# B-CAN_Board.net
KiCad netlist of a schematic drawn in EAGLE
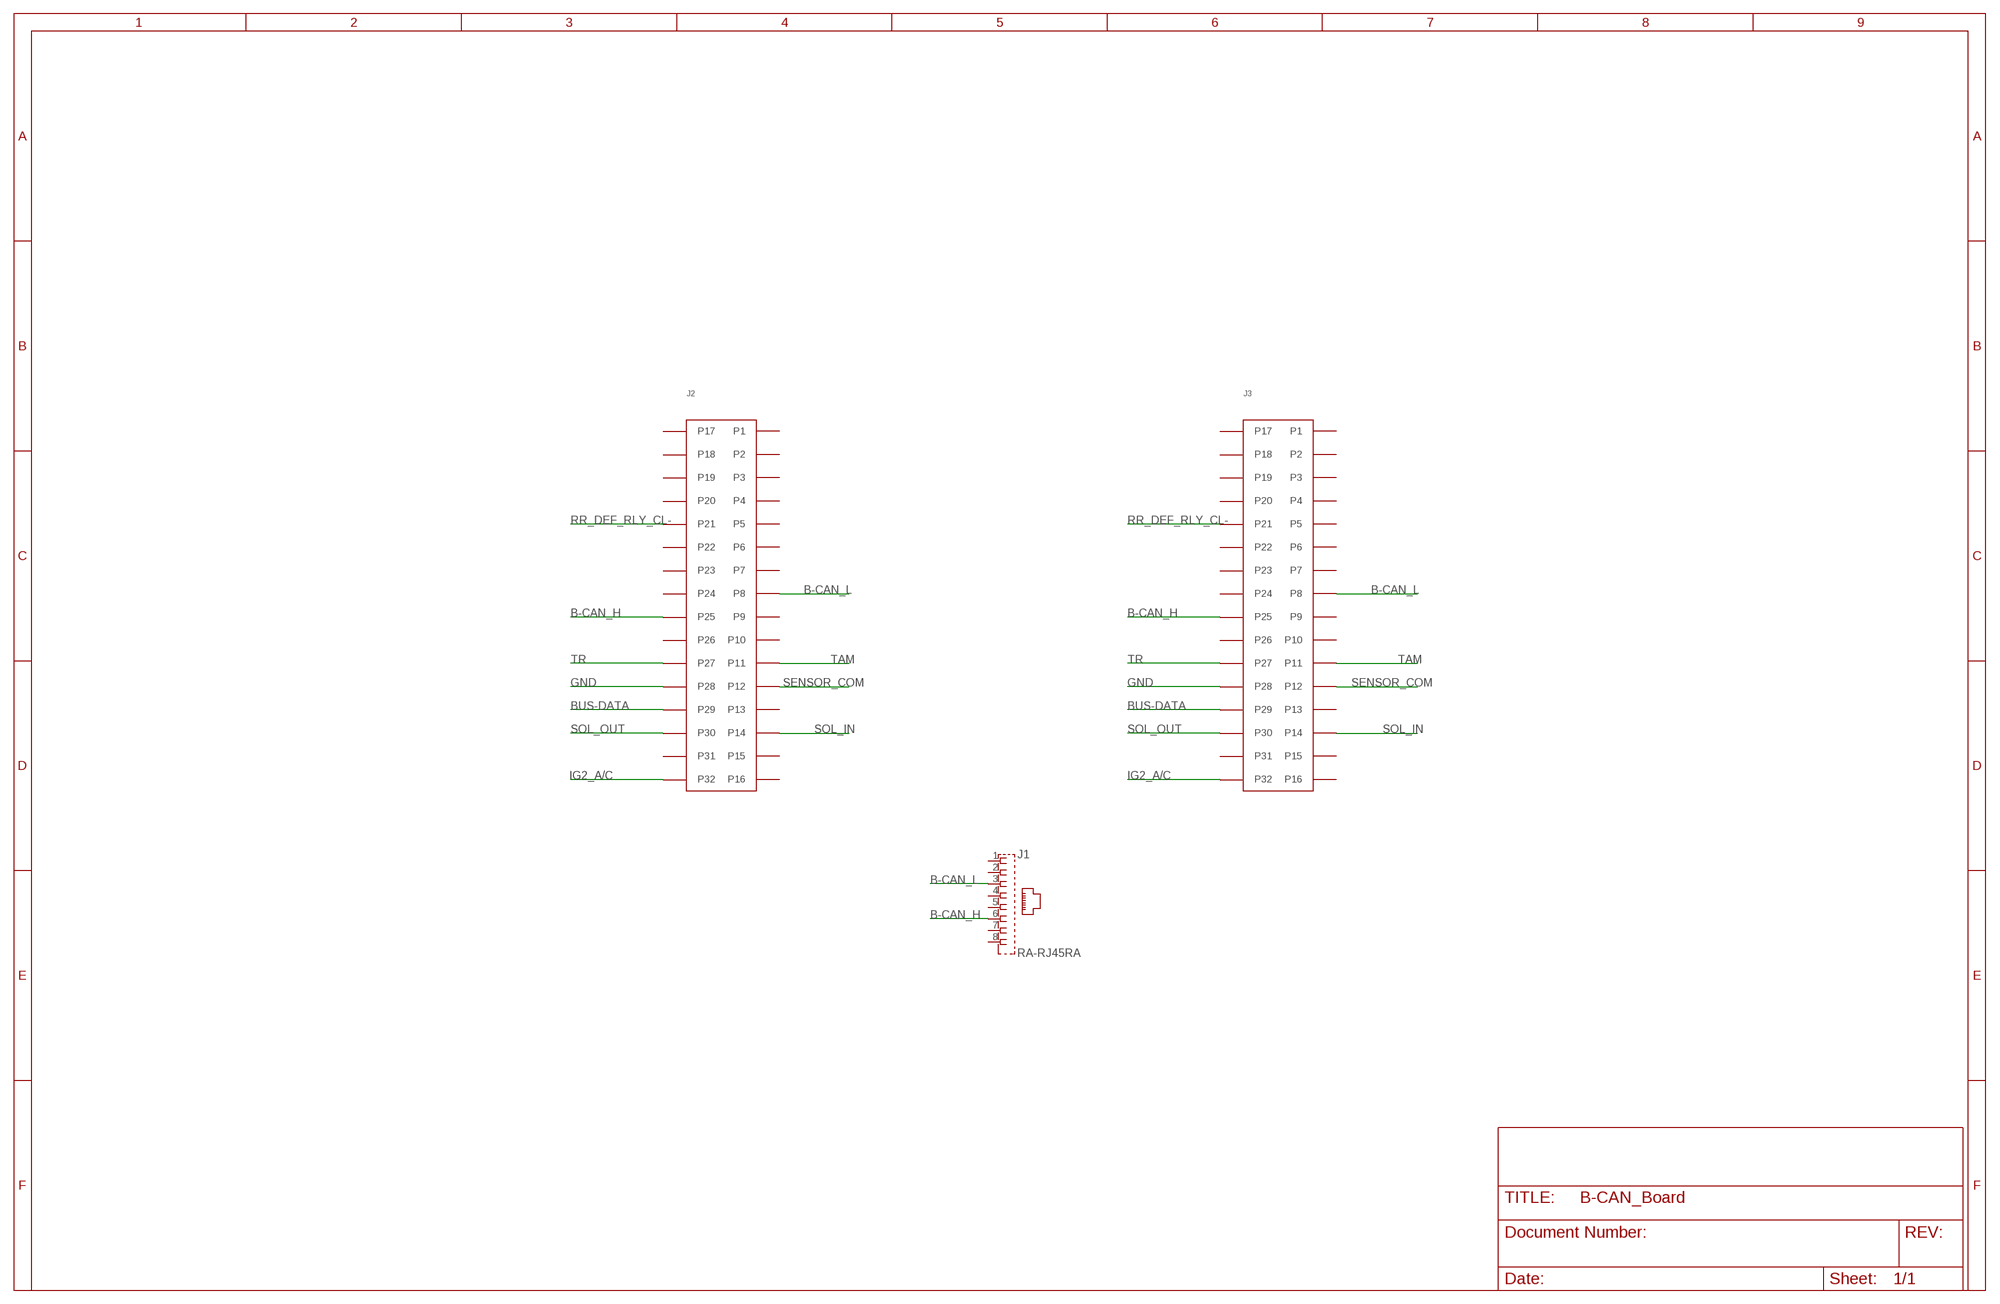
[diagram p0: schematic, sheet 1]

(export (version "E")
  (design (tool "Eeschema 10.0.6"))
  (components
    (comp (ref "J1")
      (value "RA-RJ45RA")
      (footprint "eagle-import:RA-RJ45")
      (libsource (lib "eagle-import") (part "RA-RJ45RA"))
    )
    (comp (ref "J2")
      (value "MX34032UF2")
      (footprint "eagle-import:MX34032UF2")
      (libsource (lib "eagle-import") (part "MX34032UF2"))
    )
    (comp (ref "J3")
      (value "MX34032UF2")
      (footprint "eagle-import:MX34032UF2")
      (libsource (lib "eagle-import") (part "MX34032UF2"))
    )
  )
  (nets
    (net (code "1") (name "/B-CAN_H") (class "Default")
      (node (ref "J1") (pin "6") (pinfunction "6_6") (pintype "passive"))
      (node (ref "J2") (pin "P25") (pinfunction "P25_P25") (pintype "bidirectional"))
      (node (ref "J3") (pin "P25") (pinfunction "P25_P25") (pintype "bidirectional"))
    )
    (net (code "2") (name "/B-CAN_L") (class "Default")
      (node (ref "J1") (pin "3") (pinfunction "3_3") (pintype "passive"))
      (node (ref "J2") (pin "P8") (pinfunction "P8_P8") (pintype "bidirectional"))
      (node (ref "J3") (pin "P8") (pinfunction "P8_P8") (pintype "bidirectional"))
    )
    (net (code "3") (name "/BUS-DATA") (class "Default")
      (node (ref "J2") (pin "P29") (pinfunction "P29_P29") (pintype "bidirectional"))
      (node (ref "J3") (pin "P29") (pinfunction "P29_P29") (pintype "bidirectional"))
    )
    (net (code "4") (name "/GND") (class "Default")
      (node (ref "J2") (pin "P28") (pinfunction "P28_P28") (pintype "bidirectional"))
      (node (ref "J3") (pin "P28") (pinfunction "P28_P28") (pintype "bidirectional"))
    )
    (net (code "5") (name "/IG2_A{slash}C") (class "Default")
      (node (ref "J2") (pin "P32") (pinfunction "P32_P32") (pintype "bidirectional"))
      (node (ref "J3") (pin "P32") (pinfunction "P32_P32") (pintype "bidirectional"))
    )
    (net (code "6") (name "/RR_DEF_RLY_CL-") (class "Default")
      (node (ref "J2") (pin "P21") (pinfunction "P21_P21") (pintype "bidirectional"))
      (node (ref "J3") (pin "P21") (pinfunction "P21_P21") (pintype "bidirectional"))
    )
    (net (code "7") (name "/SENSOR_COM") (class "Default")
      (node (ref "J2") (pin "P12") (pinfunction "P12_P12") (pintype "bidirectional"))
      (node (ref "J3") (pin "P12") (pinfunction "P12_P12") (pintype "bidirectional"))
    )
    (net (code "8") (name "/SOL_IN") (class "Default")
      (node (ref "J2") (pin "P14") (pinfunction "P14_P14") (pintype "bidirectional"))
      (node (ref "J3") (pin "P14") (pinfunction "P14_P14") (pintype "bidirectional"))
    )
    (net (code "9") (name "/SOL_OUT") (class "Default")
      (node (ref "J2") (pin "P30") (pinfunction "P30_P30") (pintype "bidirectional"))
      (node (ref "J3") (pin "P30") (pinfunction "P30_P30") (pintype "bidirectional"))
    )
    (net (code "10") (name "/TAM") (class "Default")
      (node (ref "J2") (pin "P11") (pinfunction "P11_P11") (pintype "bidirectional"))
      (node (ref "J3") (pin "P11") (pinfunction "P11_P11") (pintype "bidirectional"))
    )
    (net (code "11") (name "/TR") (class "Default")
      (node (ref "J2") (pin "P27") (pinfunction "P27_P27") (pintype "bidirectional"))
      (node (ref "J3") (pin "P27") (pinfunction "P27_P27") (pintype "bidirectional"))
    )
    (net (code "12") (name "unconnected-(J1-Pad1)") (class "Default")
      (node (ref "J1") (pin "1") (pinfunction "1_1") (pintype "passive"))
    )
    (net (code "13") (name "unconnected-(J1-Pad2)") (class "Default")
      (node (ref "J1") (pin "2") (pinfunction "2_2") (pintype "passive"))
    )
    (net (code "14") (name "unconnected-(J1-Pad4)") (class "Default")
      (node (ref "J1") (pin "4") (pinfunction "4_4") (pintype "passive"))
    )
    (net (code "15") (name "unconnected-(J1-Pad5)") (class "Default")
      (node (ref "J1") (pin "5") (pinfunction "5_5") (pintype "passive"))
    )
    (net (code "16") (name "unconnected-(J1-Pad7)") (class "Default")
      (node (ref "J1") (pin "7") (pinfunction "7_7") (pintype "passive"))
    )
    (net (code "17") (name "unconnected-(J1-Pad8)") (class "Default")
      (node (ref "J1") (pin "8") (pinfunction "8_8") (pintype "passive"))
    )
    (net (code "18") (name "unconnected-(J2-PadP1)") (class "Default")
      (node (ref "J2") (pin "P1") (pinfunction "P1_P1") (pintype "bidirectional"))
    )
    (net (code "19") (name "unconnected-(J2-PadP2)") (class "Default")
      (node (ref "J2") (pin "P2") (pinfunction "P2_P2") (pintype "bidirectional"))
    )
    (net (code "20") (name "unconnected-(J2-PadP3)") (class "Default")
      (node (ref "J2") (pin "P3") (pinfunction "P3_P3") (pintype "bidirectional"))
    )
    (net (code "21") (name "unconnected-(J2-PadP4)") (class "Default")
      (node (ref "J2") (pin "P4") (pinfunction "P4_P4") (pintype "bidirectional"))
    )
    (net (code "22") (name "unconnected-(J2-PadP5)") (class "Default")
      (node (ref "J2") (pin "P5") (pinfunction "P5_P5") (pintype "bidirectional"))
    )
    (net (code "23") (name "unconnected-(J2-PadP6)") (class "Default")
      (node (ref "J2") (pin "P6") (pinfunction "P6_P6") (pintype "bidirectional"))
    )
    (net (code "24") (name "unconnected-(J2-PadP7)") (class "Default")
      (node (ref "J2") (pin "P7") (pinfunction "P7_P7") (pintype "bidirectional"))
    )
    (net (code "25") (name "unconnected-(J2-PadP9)") (class "Default")
      (node (ref "J2") (pin "P9") (pinfunction "P9_P9") (pintype "bidirectional"))
    )
    (net (code "26") (name "unconnected-(J2-PadP10)") (class "Default")
      (node (ref "J2") (pin "P10") (pinfunction "P10_P10") (pintype "bidirectional"))
    )
    (net (code "27") (name "unconnected-(J2-PadP13)") (class "Default")
      (node (ref "J2") (pin "P13") (pinfunction "P13_P13") (pintype "bidirectional"))
    )
    (net (code "28") (name "unconnected-(J2-PadP15)") (class "Default")
      (node (ref "J2") (pin "P15") (pinfunction "P15_P15") (pintype "bidirectional"))
    )
    (net (code "29") (name "unconnected-(J2-PadP16)") (class "Default")
      (node (ref "J2") (pin "P16") (pinfunction "P16_P16") (pintype "bidirectional"))
    )
    (net (code "30") (name "unconnected-(J2-PadP17)") (class "Default")
      (node (ref "J2") (pin "P17") (pinfunction "P17_P17") (pintype "bidirectional"))
    )
    (net (code "31") (name "unconnected-(J2-PadP18)") (class "Default")
      (node (ref "J2") (pin "P18") (pinfunction "P18_P18") (pintype "bidirectional"))
    )
    (net (code "32") (name "unconnected-(J2-PadP19)") (class "Default")
      (node (ref "J2") (pin "P19") (pinfunction "P19_P19") (pintype "bidirectional"))
    )
    (net (code "33") (name "unconnected-(J2-PadP20)") (class "Default")
      (node (ref "J2") (pin "P20") (pinfunction "P20_P20") (pintype "bidirectional"))
    )
    (net (code "34") (name "unconnected-(J2-PadP22)") (class "Default")
      (node (ref "J2") (pin "P22") (pinfunction "P22_P22") (pintype "bidirectional"))
    )
    (net (code "35") (name "unconnected-(J2-PadP23)") (class "Default")
      (node (ref "J2") (pin "P23") (pinfunction "P23_P23") (pintype "bidirectional"))
    )
    (net (code "36") (name "unconnected-(J2-PadP24)") (class "Default")
      (node (ref "J2") (pin "P24") (pinfunction "P24_P24") (pintype "bidirectional"))
    )
    (net (code "37") (name "unconnected-(J2-PadP26)") (class "Default")
      (node (ref "J2") (pin "P26") (pinfunction "P26_P26") (pintype "bidirectional"))
    )
    (net (code "38") (name "unconnected-(J2-PadP31)") (class "Default")
      (node (ref "J2") (pin "P31") (pinfunction "P31_P31") (pintype "bidirectional"))
    )
    (net (code "39") (name "unconnected-(J3-PadP1)") (class "Default")
      (node (ref "J3") (pin "P1") (pinfunction "P1_P1") (pintype "bidirectional"))
    )
    (net (code "40") (name "unconnected-(J3-PadP2)") (class "Default")
      (node (ref "J3") (pin "P2") (pinfunction "P2_P2") (pintype "bidirectional"))
    )
    (net (code "41") (name "unconnected-(J3-PadP3)") (class "Default")
      (node (ref "J3") (pin "P3") (pinfunction "P3_P3") (pintype "bidirectional"))
    )
    (net (code "42") (name "unconnected-(J3-PadP4)") (class "Default")
      (node (ref "J3") (pin "P4") (pinfunction "P4_P4") (pintype "bidirectional"))
    )
    (net (code "43") (name "unconnected-(J3-PadP5)") (class "Default")
      (node (ref "J3") (pin "P5") (pinfunction "P5_P5") (pintype "bidirectional"))
    )
    (net (code "44") (name "unconnected-(J3-PadP6)") (class "Default")
      (node (ref "J3") (pin "P6") (pinfunction "P6_P6") (pintype "bidirectional"))
    )
    (net (code "45") (name "unconnected-(J3-PadP7)") (class "Default")
      (node (ref "J3") (pin "P7") (pinfunction "P7_P7") (pintype "bidirectional"))
    )
    (net (code "46") (name "unconnected-(J3-PadP9)") (class "Default")
      (node (ref "J3") (pin "P9") (pinfunction "P9_P9") (pintype "bidirectional"))
    )
    (net (code "47") (name "unconnected-(J3-PadP10)") (class "Default")
      (node (ref "J3") (pin "P10") (pinfunction "P10_P10") (pintype "bidirectional"))
    )
    (net (code "48") (name "unconnected-(J3-PadP13)") (class "Default")
      (node (ref "J3") (pin "P13") (pinfunction "P13_P13") (pintype "bidirectional"))
    )
    (net (code "49") (name "unconnected-(J3-PadP15)") (class "Default")
      (node (ref "J3") (pin "P15") (pinfunction "P15_P15") (pintype "bidirectional"))
    )
    (net (code "50") (name "unconnected-(J3-PadP16)") (class "Default")
      (node (ref "J3") (pin "P16") (pinfunction "P16_P16") (pintype "bidirectional"))
    )
    (net (code "51") (name "unconnected-(J3-PadP17)") (class "Default")
      (node (ref "J3") (pin "P17") (pinfunction "P17_P17") (pintype "bidirectional"))
    )
    (net (code "52") (name "unconnected-(J3-PadP18)") (class "Default")
      (node (ref "J3") (pin "P18") (pinfunction "P18_P18") (pintype "bidirectional"))
    )
    (net (code "53") (name "unconnected-(J3-PadP19)") (class "Default")
      (node (ref "J3") (pin "P19") (pinfunction "P19_P19") (pintype "bidirectional"))
    )
    (net (code "54") (name "unconnected-(J3-PadP20)") (class "Default")
      (node (ref "J3") (pin "P20") (pinfunction "P20_P20") (pintype "bidirectional"))
    )
    (net (code "55") (name "unconnected-(J3-PadP22)") (class "Default")
      (node (ref "J3") (pin "P22") (pinfunction "P22_P22") (pintype "bidirectional"))
    )
    (net (code "56") (name "unconnected-(J3-PadP23)") (class "Default")
      (node (ref "J3") (pin "P23") (pinfunction "P23_P23") (pintype "bidirectional"))
    )
    (net (code "57") (name "unconnected-(J3-PadP24)") (class "Default")
      (node (ref "J3") (pin "P24") (pinfunction "P24_P24") (pintype "bidirectional"))
    )
    (net (code "58") (name "unconnected-(J3-PadP26)") (class "Default")
      (node (ref "J3") (pin "P26") (pinfunction "P26_P26") (pintype "bidirectional"))
    )
    (net (code "59") (name "unconnected-(J3-PadP31)") (class "Default")
      (node (ref "J3") (pin "P31") (pinfunction "P31_P31") (pintype "bidirectional"))
    )
  )
)
